# TLC5955.net
KiCad netlist of a schematic drawn in EAGLE
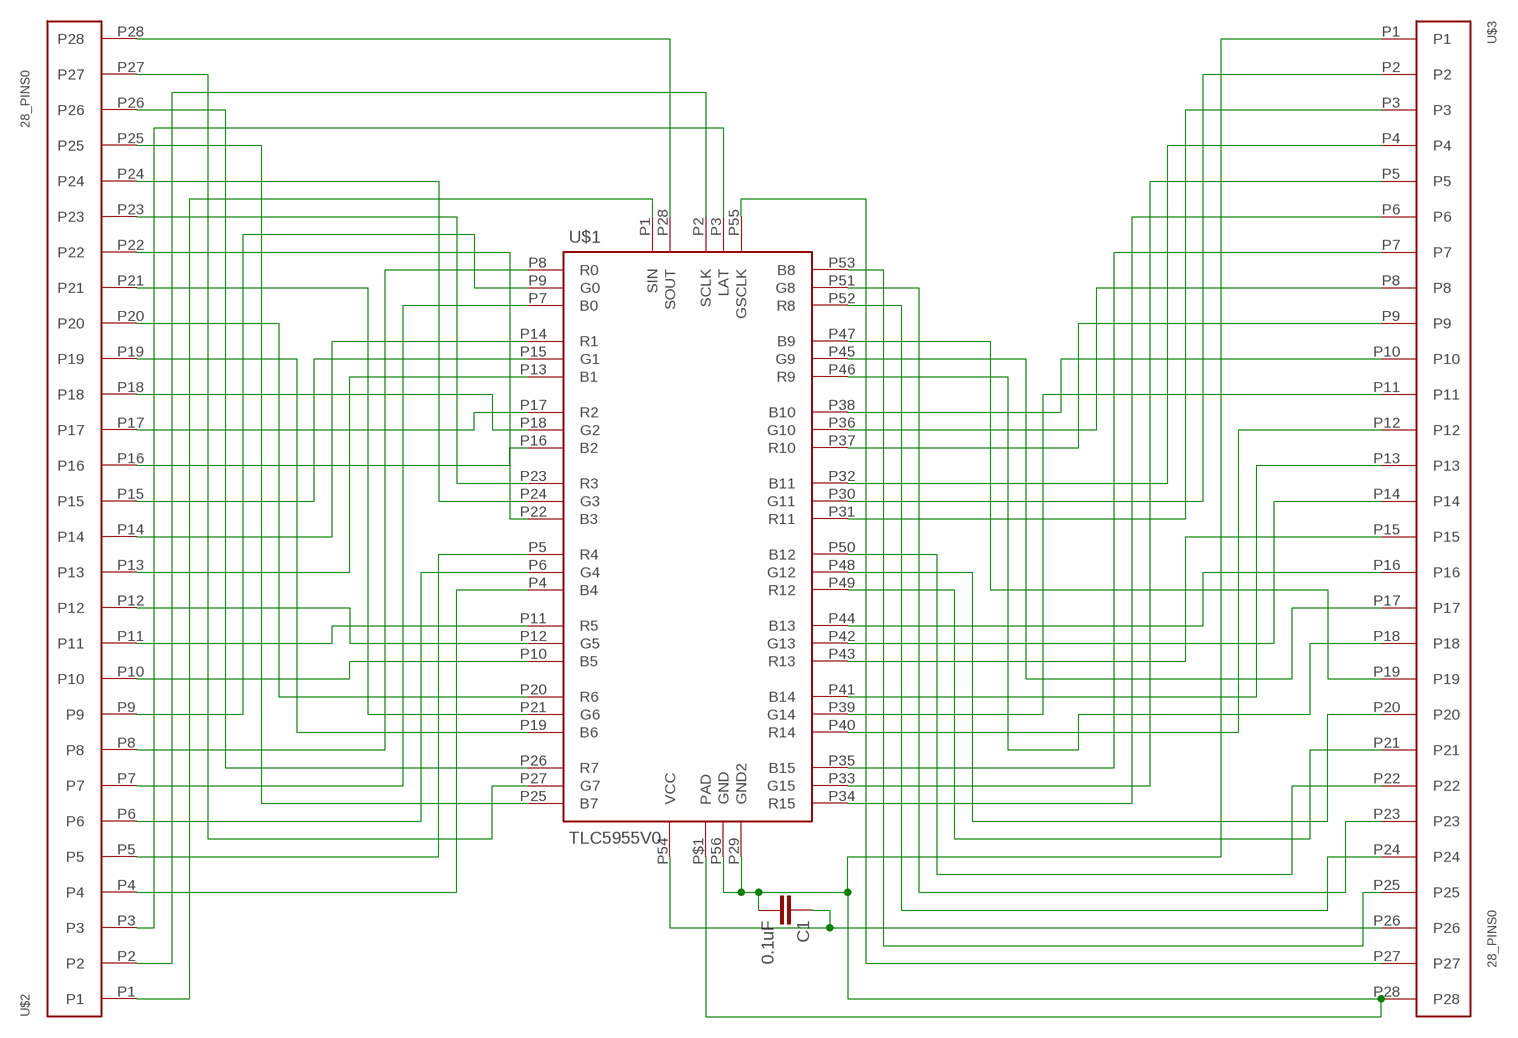
[diagram p0: schematic, sheet 1]

(export (version "E")
  (design (tool "Eeschema 10.0.6"))
  (components
    (comp (ref "C1")
      (value "0.1uF")
      (footprint "eagle-import:0603-CAP")
      (libsource (lib "eagle-import") (part "0.1UF-25V(+80/-20%)(0603)"))
    )
    (comp (ref "U$1")
      (value "TLC5955V0")
      (footprint "eagle-import:56-HTSSOP")
      (libsource (lib "eagle-import") (part "TLC5955V0"))
    )
    (comp (ref "U$2")
      (value "28_PINS0")
      (footprint "eagle-import:28PIN_HOLES")
      (libsource (lib "eagle-import") (part "28_PINS0"))
    )
    (comp (ref "U$3")
      (value "28_PINS0")
      (footprint "eagle-import:28PIN_HOLES")
      (libsource (lib "eagle-import") (part "28_PINS0"))
    )
  )
  (nets
    (net (code "1") (name "Net-(U$1-B0)") (class "Default")
      (node (ref "U$1") (pin "P7") (pinfunction "B0_P7") (pintype "bidirectional"))
      (node (ref "U$2") (pin "P7") (pinfunction "P7_P7") (pintype "bidirectional"))
    )
    (net (code "2") (name "Net-(U$1-B1)") (class "Default")
      (node (ref "U$1") (pin "P13") (pinfunction "B1_P13") (pintype "bidirectional"))
      (node (ref "U$2") (pin "P13") (pinfunction "P13_P13") (pintype "bidirectional"))
    )
    (net (code "3") (name "Net-(U$1-B2)") (class "Default")
      (node (ref "U$1") (pin "P16") (pinfunction "B2_P16") (pintype "bidirectional"))
      (node (ref "U$2") (pin "P16") (pinfunction "P16_P16") (pintype "bidirectional"))
    )
    (net (code "4") (name "Net-(U$1-B3)") (class "Default")
      (node (ref "U$1") (pin "P22") (pinfunction "B3_P22") (pintype "bidirectional"))
      (node (ref "U$2") (pin "P22") (pinfunction "P22_P22") (pintype "bidirectional"))
    )
    (net (code "5") (name "Net-(U$1-B4)") (class "Default")
      (node (ref "U$1") (pin "P4") (pinfunction "B4_P4") (pintype "bidirectional"))
      (node (ref "U$2") (pin "P4") (pinfunction "P4_P4") (pintype "bidirectional"))
    )
    (net (code "6") (name "Net-(U$1-B5)") (class "Default")
      (node (ref "U$1") (pin "P10") (pinfunction "B5_P10") (pintype "bidirectional"))
      (node (ref "U$2") (pin "P10") (pinfunction "P10_P10") (pintype "bidirectional"))
    )
    (net (code "7") (name "Net-(U$1-B6)") (class "Default")
      (node (ref "U$1") (pin "P19") (pinfunction "B6_P19") (pintype "bidirectional"))
      (node (ref "U$2") (pin "P19") (pinfunction "P19_P19") (pintype "bidirectional"))
    )
    (net (code "8") (name "Net-(U$1-B7)") (class "Default")
      (node (ref "U$1") (pin "P25") (pinfunction "B7_P25") (pintype "bidirectional"))
      (node (ref "U$2") (pin "P25") (pinfunction "P25_P25") (pintype "bidirectional"))
    )
    (net (code "9") (name "Net-(U$1-B8)") (class "Default")
      (node (ref "U$1") (pin "P53") (pinfunction "B8_P53") (pintype "bidirectional"))
      (node (ref "U$3") (pin "P25") (pinfunction "P25_P25") (pintype "bidirectional"))
    )
    (net (code "10") (name "Net-(U$1-B9)") (class "Default")
      (node (ref "U$1") (pin "P47") (pinfunction "B9_P47") (pintype "bidirectional"))
      (node (ref "U$3") (pin "P19") (pinfunction "P19_P19") (pintype "bidirectional"))
    )
    (net (code "11") (name "Net-(U$1-B10)") (class "Default")
      (node (ref "U$1") (pin "P38") (pinfunction "B10_P38") (pintype "bidirectional"))
      (node (ref "U$3") (pin "P10") (pinfunction "P10_P10") (pintype "bidirectional"))
    )
    (net (code "12") (name "Net-(U$1-B11)") (class "Default")
      (node (ref "U$1") (pin "P32") (pinfunction "B11_P32") (pintype "bidirectional"))
      (node (ref "U$3") (pin "P4") (pinfunction "P4_P4") (pintype "bidirectional"))
    )
    (net (code "13") (name "Net-(U$1-B12)") (class "Default")
      (node (ref "U$1") (pin "P50") (pinfunction "B12_P50") (pintype "bidirectional"))
      (node (ref "U$3") (pin "P22") (pinfunction "P22_P22") (pintype "bidirectional"))
    )
    (net (code "14") (name "Net-(U$1-B13)") (class "Default")
      (node (ref "U$1") (pin "P44") (pinfunction "B13_P44") (pintype "bidirectional"))
      (node (ref "U$3") (pin "P16") (pinfunction "P16_P16") (pintype "bidirectional"))
    )
    (net (code "15") (name "Net-(U$1-B14)") (class "Default")
      (node (ref "U$1") (pin "P41") (pinfunction "B14_P41") (pintype "bidirectional"))
      (node (ref "U$3") (pin "P13") (pinfunction "P13_P13") (pintype "bidirectional"))
    )
    (net (code "16") (name "Net-(U$1-B15)") (class "Default")
      (node (ref "U$1") (pin "P35") (pinfunction "B15_P35") (pintype "bidirectional"))
      (node (ref "U$3") (pin "P7") (pinfunction "P7_P7") (pintype "bidirectional"))
    )
    (net (code "17") (name "Net-(U$1-G0)") (class "Default")
      (node (ref "U$1") (pin "P9") (pinfunction "G0_P9") (pintype "bidirectional"))
      (node (ref "U$2") (pin "P9") (pinfunction "P9_P9") (pintype "bidirectional"))
    )
    (net (code "18") (name "Net-(U$1-G1)") (class "Default")
      (node (ref "U$1") (pin "P15") (pinfunction "G1_P15") (pintype "bidirectional"))
      (node (ref "U$2") (pin "P15") (pinfunction "P15_P15") (pintype "bidirectional"))
    )
    (net (code "19") (name "Net-(U$1-G2)") (class "Default")
      (node (ref "U$1") (pin "P18") (pinfunction "G2_P18") (pintype "bidirectional"))
      (node (ref "U$2") (pin "P18") (pinfunction "P18_P18") (pintype "bidirectional"))
    )
    (net (code "20") (name "Net-(U$1-G3)") (class "Default")
      (node (ref "U$1") (pin "P24") (pinfunction "G3_P24") (pintype "bidirectional"))
      (node (ref "U$2") (pin "P24") (pinfunction "P24_P24") (pintype "bidirectional"))
    )
    (net (code "21") (name "Net-(U$1-G4)") (class "Default")
      (node (ref "U$1") (pin "P6") (pinfunction "G4_P6") (pintype "bidirectional"))
      (node (ref "U$2") (pin "P6") (pinfunction "P6_P6") (pintype "bidirectional"))
    )
    (net (code "22") (name "Net-(U$1-G5)") (class "Default")
      (node (ref "U$1") (pin "P12") (pinfunction "G5_P12") (pintype "bidirectional"))
      (node (ref "U$2") (pin "P12") (pinfunction "P12_P12") (pintype "bidirectional"))
    )
    (net (code "23") (name "Net-(U$1-G6)") (class "Default")
      (node (ref "U$1") (pin "P21") (pinfunction "G6_P21") (pintype "bidirectional"))
      (node (ref "U$2") (pin "P21") (pinfunction "P21_P21") (pintype "bidirectional"))
    )
    (net (code "24") (name "Net-(U$1-G7)") (class "Default")
      (node (ref "U$1") (pin "P27") (pinfunction "G7_P27") (pintype "bidirectional"))
      (node (ref "U$2") (pin "P27") (pinfunction "P27_P27") (pintype "bidirectional"))
    )
    (net (code "25") (name "Net-(U$1-G8)") (class "Default")
      (node (ref "U$1") (pin "P51") (pinfunction "G8_P51") (pintype "bidirectional"))
      (node (ref "U$3") (pin "P23") (pinfunction "P23_P23") (pintype "bidirectional"))
    )
    (net (code "26") (name "Net-(U$1-G9)") (class "Default")
      (node (ref "U$1") (pin "P45") (pinfunction "G9_P45") (pintype "bidirectional"))
      (node (ref "U$3") (pin "P17") (pinfunction "P17_P17") (pintype "bidirectional"))
    )
    (net (code "27") (name "Net-(U$1-G10)") (class "Default")
      (node (ref "U$1") (pin "P36") (pinfunction "G10_P36") (pintype "bidirectional"))
      (node (ref "U$3") (pin "P8") (pinfunction "P8_P8") (pintype "bidirectional"))
    )
    (net (code "28") (name "Net-(U$1-G11)") (class "Default")
      (node (ref "U$1") (pin "P30") (pinfunction "G11_P30") (pintype "bidirectional"))
      (node (ref "U$3") (pin "P2") (pinfunction "P2_P2") (pintype "bidirectional"))
    )
    (net (code "29") (name "Net-(U$1-G12)") (class "Default")
      (node (ref "U$1") (pin "P48") (pinfunction "G12_P48") (pintype "bidirectional"))
      (node (ref "U$3") (pin "P20") (pinfunction "P20_P20") (pintype "bidirectional"))
    )
    (net (code "30") (name "Net-(U$1-G13)") (class "Default")
      (node (ref "U$1") (pin "P42") (pinfunction "G13_P42") (pintype "bidirectional"))
      (node (ref "U$3") (pin "P14") (pinfunction "P14_P14") (pintype "bidirectional"))
    )
    (net (code "31") (name "Net-(U$1-G14)") (class "Default")
      (node (ref "U$1") (pin "P39") (pinfunction "G14_P39") (pintype "bidirectional"))
      (node (ref "U$3") (pin "P11") (pinfunction "P11_P11") (pintype "bidirectional"))
    )
    (net (code "32") (name "Net-(U$1-G15)") (class "Default")
      (node (ref "U$1") (pin "P33") (pinfunction "G15_P33") (pintype "bidirectional"))
      (node (ref "U$3") (pin "P5") (pinfunction "P5_P5") (pintype "bidirectional"))
    )
    (net (code "33") (name "Net-(U$1-GND)") (class "Default")
      (node (ref "C1") (pin "2") (pinfunction "2_2") (pintype "passive"))
      (node (ref "U$1") (pin "P$1") (pinfunction "PAD_P$1") (pintype "bidirectional"))
      (node (ref "U$1") (pin "P29") (pinfunction "GND2_P29") (pintype "bidirectional"))
      (node (ref "U$1") (pin "P56") (pinfunction "GND_P56") (pintype "bidirectional"))
      (node (ref "U$3") (pin "P1") (pinfunction "P1_P1") (pintype "bidirectional"))
      (node (ref "U$3") (pin "P28") (pinfunction "P28_P28") (pintype "bidirectional"))
    )
    (net (code "34") (name "Net-(U$1-GSCLK)") (class "Default")
      (node (ref "U$1") (pin "P55") (pinfunction "GSCLK_P55") (pintype "bidirectional"))
      (node (ref "U$3") (pin "P27") (pinfunction "P27_P27") (pintype "bidirectional"))
    )
    (net (code "35") (name "Net-(U$1-LAT)") (class "Default")
      (node (ref "U$1") (pin "P3") (pinfunction "LAT_P3") (pintype "bidirectional"))
      (node (ref "U$2") (pin "P3") (pinfunction "P3_P3") (pintype "bidirectional"))
    )
    (net (code "36") (name "Net-(U$1-R0)") (class "Default")
      (node (ref "U$1") (pin "P8") (pinfunction "R0_P8") (pintype "bidirectional"))
      (node (ref "U$2") (pin "P8") (pinfunction "P8_P8") (pintype "bidirectional"))
    )
    (net (code "37") (name "Net-(U$1-R1)") (class "Default")
      (node (ref "U$1") (pin "P14") (pinfunction "R1_P14") (pintype "bidirectional"))
      (node (ref "U$2") (pin "P14") (pinfunction "P14_P14") (pintype "bidirectional"))
    )
    (net (code "38") (name "Net-(U$1-R2)") (class "Default")
      (node (ref "U$1") (pin "P17") (pinfunction "R2_P17") (pintype "bidirectional"))
      (node (ref "U$2") (pin "P17") (pinfunction "P17_P17") (pintype "bidirectional"))
    )
    (net (code "39") (name "Net-(U$1-R3)") (class "Default")
      (node (ref "U$1") (pin "P23") (pinfunction "R3_P23") (pintype "bidirectional"))
      (node (ref "U$2") (pin "P23") (pinfunction "P23_P23") (pintype "bidirectional"))
    )
    (net (code "40") (name "Net-(U$1-R4)") (class "Default")
      (node (ref "U$1") (pin "P5") (pinfunction "R4_P5") (pintype "bidirectional"))
      (node (ref "U$2") (pin "P5") (pinfunction "P5_P5") (pintype "bidirectional"))
    )
    (net (code "41") (name "Net-(U$1-R5)") (class "Default")
      (node (ref "U$1") (pin "P11") (pinfunction "R5_P11") (pintype "bidirectional"))
      (node (ref "U$2") (pin "P11") (pinfunction "P11_P11") (pintype "bidirectional"))
    )
    (net (code "42") (name "Net-(U$1-R6)") (class "Default")
      (node (ref "U$1") (pin "P20") (pinfunction "R6_P20") (pintype "bidirectional"))
      (node (ref "U$2") (pin "P20") (pinfunction "P20_P20") (pintype "bidirectional"))
    )
    (net (code "43") (name "Net-(U$1-R7)") (class "Default")
      (node (ref "U$1") (pin "P26") (pinfunction "R7_P26") (pintype "bidirectional"))
      (node (ref "U$2") (pin "P26") (pinfunction "P26_P26") (pintype "bidirectional"))
    )
    (net (code "44") (name "Net-(U$1-R8)") (class "Default")
      (node (ref "U$1") (pin "P52") (pinfunction "R8_P52") (pintype "bidirectional"))
      (node (ref "U$3") (pin "P24") (pinfunction "P24_P24") (pintype "bidirectional"))
    )
    (net (code "45") (name "Net-(U$1-R9)") (class "Default")
      (node (ref "U$1") (pin "P46") (pinfunction "R9_P46") (pintype "bidirectional"))
      (node (ref "U$3") (pin "P18") (pinfunction "P18_P18") (pintype "bidirectional"))
    )
    (net (code "46") (name "Net-(U$1-R10)") (class "Default")
      (node (ref "U$1") (pin "P37") (pinfunction "R10_P37") (pintype "bidirectional"))
      (node (ref "U$3") (pin "P9") (pinfunction "P9_P9") (pintype "bidirectional"))
    )
    (net (code "47") (name "Net-(U$1-R11)") (class "Default")
      (node (ref "U$1") (pin "P31") (pinfunction "R11_P31") (pintype "bidirectional"))
      (node (ref "U$3") (pin "P3") (pinfunction "P3_P3") (pintype "bidirectional"))
    )
    (net (code "48") (name "Net-(U$1-R12)") (class "Default")
      (node (ref "U$1") (pin "P49") (pinfunction "R12_P49") (pintype "bidirectional"))
      (node (ref "U$3") (pin "P21") (pinfunction "P21_P21") (pintype "bidirectional"))
    )
    (net (code "49") (name "Net-(U$1-R13)") (class "Default")
      (node (ref "U$1") (pin "P43") (pinfunction "R13_P43") (pintype "bidirectional"))
      (node (ref "U$3") (pin "P15") (pinfunction "P15_P15") (pintype "bidirectional"))
    )
    (net (code "50") (name "Net-(U$1-R14)") (class "Default")
      (node (ref "U$1") (pin "P40") (pinfunction "R14_P40") (pintype "bidirectional"))
      (node (ref "U$3") (pin "P12") (pinfunction "P12_P12") (pintype "bidirectional"))
    )
    (net (code "51") (name "Net-(U$1-R15)") (class "Default")
      (node (ref "U$1") (pin "P34") (pinfunction "R15_P34") (pintype "bidirectional"))
      (node (ref "U$3") (pin "P6") (pinfunction "P6_P6") (pintype "bidirectional"))
    )
    (net (code "52") (name "Net-(U$1-SCLK)") (class "Default")
      (node (ref "U$1") (pin "P2") (pinfunction "SCLK_P2") (pintype "bidirectional"))
      (node (ref "U$2") (pin "P2") (pinfunction "P2_P2") (pintype "bidirectional"))
    )
    (net (code "53") (name "Net-(U$1-SIN)") (class "Default")
      (node (ref "U$1") (pin "P1") (pinfunction "SIN_P1") (pintype "bidirectional"))
      (node (ref "U$2") (pin "P1") (pinfunction "P1_P1") (pintype "bidirectional"))
    )
    (net (code "54") (name "Net-(U$1-SOUT)") (class "Default")
      (node (ref "U$1") (pin "P28") (pinfunction "SOUT_P28") (pintype "bidirectional"))
      (node (ref "U$2") (pin "P28") (pinfunction "P28_P28") (pintype "bidirectional"))
    )
    (net (code "55") (name "Net-(U$1-VCC)") (class "Default")
      (node (ref "C1") (pin "1") (pinfunction "1_1") (pintype "passive"))
      (node (ref "U$1") (pin "P54") (pinfunction "VCC_P54") (pintype "bidirectional"))
      (node (ref "U$3") (pin "P26") (pinfunction "P26_P26") (pintype "bidirectional"))
    )
  )
)
